# BATTERY.net
KiCad netlist of a schematic drawn in Altium Designer
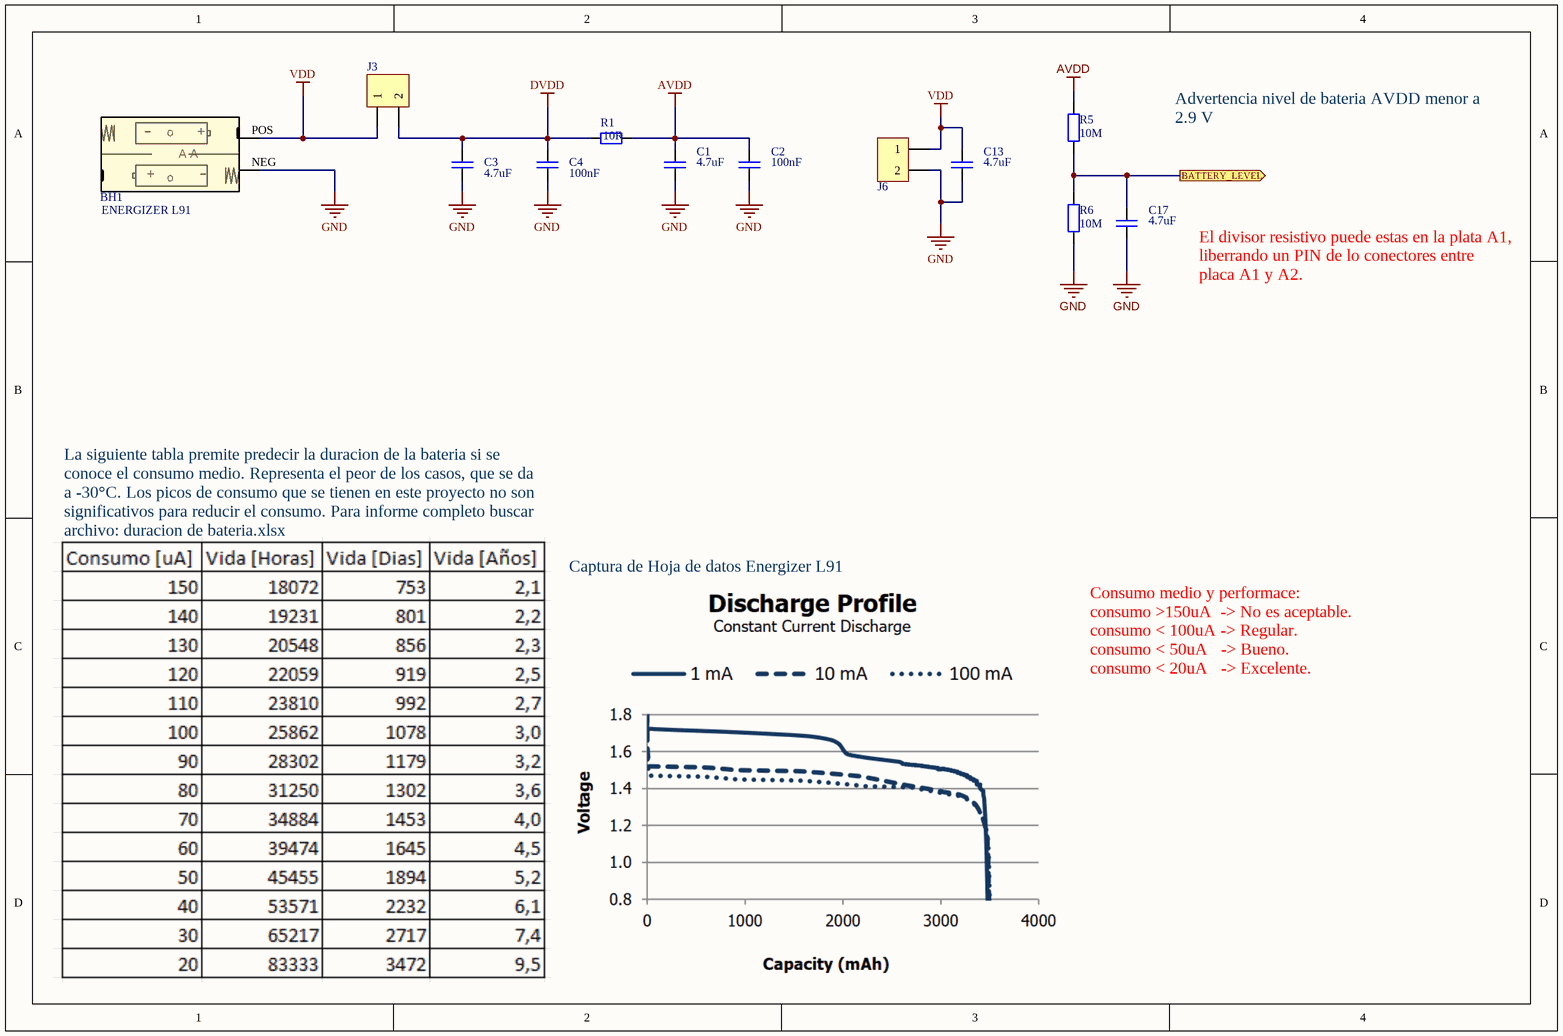
[diagram p0: BATTERY.SchDoc]

(export (version "E")
  (design (tool "Eeschema 10.0.6"))
  (components
    (comp (ref "BH1")
      (value "ENERGIZER L91")
      (footprint "BATTERY_HOLDER_2XAA")
      (description "2 x AA through hole economic type")
      (fields (field (name "MANUFACTURER") "Keystone") (field (name "MANUFACTURER PART NUMBER") "2462"))
      (libsource (lib "Battery_Holders") (part "2462"))
    )
    (comp (ref "C1")
      (value "4.7uF")
      (footprint "CAP_SM0805_YAGEOCC2_N")
      (description "CAP 4.7uF SM0805 X5R 10V YAGEO CC2")
      (fields
        (field (name "MANUFACTURER") "Yageo")
        (field (name "MANUFACTURER PART NUMBER") "CC0805KRX5R6BB475")
      )
      (libsource (lib "Yageo") (part "CC0805KRX5R6BB475"))
    )
    (comp (ref "C2")
      (value "100nF")
      (footprint "CAP_SM0805_YAGEOCC2_N")
      (description "CAP 100nF SM0805 X7R 25V YAGEO CC2")
      (fields
        (field (name "MANUFACTURER") "Yageo")
        (field (name "MANUFACTURER PART NUMBER") "CC0805KRX7R8BB104")
      )
      (libsource (lib "Yageo") (part "CC0805KRX7R8BB104"))
    )
    (comp (ref "C3")
      (value "4.7uF")
      (footprint "CAP_SM0805_YAGEOCC2_N")
      (description "CAP 4.7uF SM0805 X5R 10V YAGEO CC2")
      (fields
        (field (name "MANUFACTURER") "Yageo")
        (field (name "MANUFACTURER PART NUMBER") "CC0805KRX5R6BB475")
      )
      (libsource (lib "Yageo") (part "CC0805KRX5R6BB475"))
    )
    (comp (ref "C4")
      (value "100nF")
      (footprint "CAP_SM0805_YAGEOCC2_N")
      (description "CAP 100nF SM0805 X7R 25V YAGEO CC2")
      (fields
        (field (name "MANUFACTURER") "Yageo")
        (field (name "MANUFACTURER PART NUMBER") "CC0805KRX7R8BB104")
      )
      (libsource (lib "Yageo") (part "CC0805KRX7R8BB104"))
    )
    (comp (ref "C13")
      (value "4.7uF")
      (footprint "CAP_SM0805_YAGEOCC2_N")
      (description "CAP 4.7uF SM0805 X5R 10V YAGEO CC2")
      (fields
        (field (name "MANUFACTURER") "Yageo")
        (field (name "MANUFACTURER PART NUMBER") "CC0805KRX5R6BB475")
      )
      (libsource (lib "Yageo") (part "CC0805KRX5R6BB475"))
    )
    (comp (ref "C17")
      (value "4.7uF")
      (footprint "CAP_SM0805_YAGEOCC2_N")
      (description "CAP 4.7uF SM0805 X5R 10V YAGEO CC2")
      (fields
        (field (name "MANUFACTURER") "Yageo")
        (field (name "MANUFACTURER PART NUMBER") "CC0805KRX5R6BB475")
      )
      (libsource (lib "Yageo") (part "CC0805KRX5R6BB475"))
    )
    (comp (ref "J3")
      (value "Usar Equivalente")
      (footprint "HEADER PIN 1X2")
      (description "1 x 2 - true hole  2.54mm - Pb free")
      (fields
        (field (name "MANUFACTURER") "Amphenol ICC")
        (field (name "MANUFACTURER PART NUMBER") "54101-T0600LF")
      )
      (libsource (lib "") (part "54101-T0600LF-CUT-2_1"))
    )
    (comp (ref "J6")
      (value "Usar Equivalente")
      (footprint "HEADER PIN 1X2")
      (description "1 x 2 - true hole  2.54mm - Pb free")
      (fields
        (field (name "MANUFACTURER") "Amphenol ICC")
        (field (name "MANUFACTURER PART NUMBER") "54101-T0600LF")
      )
      (libsource (lib "header_pin") (part "54101-T0600LF-CUT-2"))
    )
    (comp (ref "R1")
      (value "10R")
      (footprint "RES_SM0805_YAGEORC_N")
      (description "RES 10R SM0805 YAGEO RC_L")
      (fields
        (field (name "MANUFACTURER") "Yageo")
        (field (name "MANUFACTURER PART NUMBER") "RC0805FR-0710RL")
      )
      (libsource (lib "Yageo") (part "RC0805FR-0710RL"))
    )
    (comp (ref "R5")
      (value "10M")
      (footprint "RES_SM0805_YAGEORC_N")
      (description "RES 10M SM0805 YAGEO RC_L")
      (fields
        (field (name "MANUFACTURER") "Yageo")
        (field (name "MANUFACTURER PART NUMBER") "RC0805FR-0710ML")
      )
      (libsource (lib "Yageo") (part "RC0805FR-0710ML"))
    )
    (comp (ref "R6")
      (value "10M")
      (footprint "RES_SM0805_YAGEORC_N")
      (description "RES 10M SM0805 YAGEO RC_L")
      (fields
        (field (name "MANUFACTURER") "Yageo")
        (field (name "MANUFACTURER PART NUMBER") "RC0805FR-0710ML")
      )
      (libsource (lib "Yageo") (part "RC0805FR-0710ML"))
    )
  )
  (nets
    (net (code "1") (name "/BATTERY_LEVEL") (class "Default")
      (node (ref "C17") (pin "1") (pintype "passive"))
      (node (ref "R5") (pin "1") (pintype "passive"))
      (node (ref "R6") (pin "2") (pintype "passive"))
    )
    (net (code "2") (name "AVDD") (class "Default")
      (node (ref "C1") (pin "1") (pintype "passive"))
      (node (ref "C2") (pin "1") (pintype "passive"))
      (node (ref "R1") (pin "2") (pintype "passive"))
      (node (ref "R5") (pin "2") (pintype "passive"))
    )
    (net (code "3") (name "DVDD") (class "Default")
      (node (ref "C3") (pin "1") (pintype "passive"))
      (node (ref "C4") (pin "1") (pintype "passive"))
      (node (ref "J3") (pin "2") (pinfunction "2_2") (pintype "passive"))
      (node (ref "R1") (pin "1") (pintype "passive"))
    )
    (net (code "4") (name "GND") (class "Default")
      (node (ref "BH1") (pin "NEG") (pinfunction "NEG_NEG") (pintype "passive"))
      (node (ref "C1") (pin "2") (pintype "passive"))
      (node (ref "C13") (pin "2") (pintype "passive"))
      (node (ref "C17") (pin "2") (pintype "passive"))
      (node (ref "C2") (pin "2") (pintype "passive"))
      (node (ref "C3") (pin "2") (pintype "passive"))
      (node (ref "C4") (pin "2") (pintype "passive"))
      (node (ref "J6") (pin "2") (pinfunction "2_2") (pintype "passive"))
      (node (ref "R6") (pin "1") (pintype "passive"))
    )
    (net (code "5") (name "VDD") (class "Default")
      (node (ref "BH1") (pin "POS") (pinfunction "POS_POS") (pintype "passive"))
      (node (ref "C13") (pin "1") (pintype "passive"))
      (node (ref "J3") (pin "1") (pinfunction "1_1") (pintype "passive"))
      (node (ref "J6") (pin "1") (pinfunction "1_1") (pintype "passive"))
    )
  )
)
